# Sheet1.net
KiCad netlist of a schematic drawn in Altium Designer
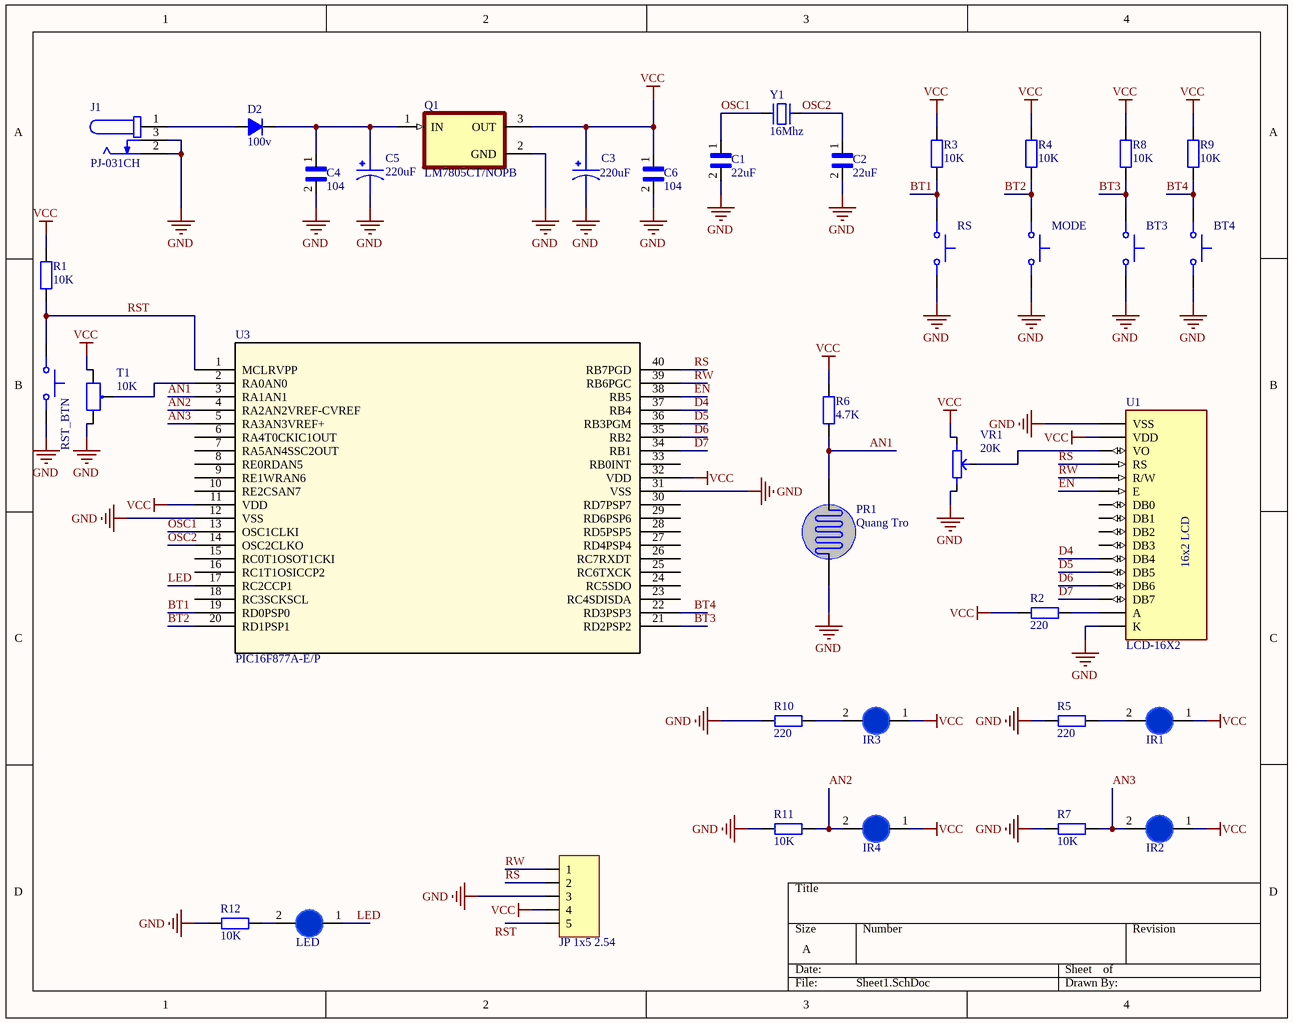
[diagram p0: Sheet1.SchDoc]

(export (version "E")
  (design (tool "Eeschema 10.0.6"))
  (components
    (comp (ref "BT3")
      (value "B3WN-6002")
      (footprint "SW_B3WN-6002")
      (description "Tactile Switch SPST-NO Top Actuated Through Hole")
      (fields (field (name "MF") "Omron Electronics"))
      (libsource (lib "button") (part "B3WN-6002"))
    )
    (comp (ref "BT4")
      (value "B3WN-6002")
      (footprint "SW_B3WN-6002")
      (description "Tactile Switch SPST-NO Top Actuated Through Hole")
      (fields (field (name "MF") "Omron Electronics"))
      (libsource (lib "button") (part "B3WN-6002"))
    )
    (comp (ref "C1")
      (value "22uF")
      (footprint "CAPRB250W50L550T350H600")
      (description "10 ÂµF Â±10% 50V Ceramic Capacitor X5R Radial")
      (fields (field (name "MF") "TDK") (field (name "MP") "FG16X5R1H106KRT00"))
      (libsource (lib "tu gom") (part "FG16X5R1H106KRT00"))
    )
    (comp (ref "C2")
      (value "22uF")
      (footprint "CAPRB250W50L550T350H600")
      (description "10 ÂµF Â±10% 50V Ceramic Capacitor X5R Radial")
      (fields (field (name "MF") "TDK") (field (name "MP") "FG16X5R1H106KRT00"))
      (libsource (lib "tu gom") (part "FG16X5R1H106KRT00"))
    )
    (comp (ref "C3")
      (value "220uF")
      (footprint "CAPPRD500W60D1330H2700")
      (description "4700 ÂµF 10 V Aluminum Electrolytic Capacitors Radial, Can 98.8mOhm @ 120Hz 2000 Hrs @ 85Â°C")
      (fields (field (name "MF") "Illinois Capacitor") (field (name "MP") "478CKS010M"))
      (libsource (lib "ALUCAP") (part "478CKS010M"))
    )
    (comp (ref "C4")
      (value "104")
      (footprint "CAPRB250W50L550T350H600")
      (description "10 ÂµF Â±10% 50V Ceramic Capacitor X5R Radial")
      (fields (field (name "MF") "TDK") (field (name "MP") "FG16X5R1H106KRT00"))
      (libsource (lib "tu gom") (part "FG16X5R1H106KRT00"))
    )
    (comp (ref "C5")
      (value "220uF")
      (footprint "CAPPRD500W60D1330H2700")
      (description "4700 ÂµF 10 V Aluminum Electrolytic Capacitors Radial, Can 98.8mOhm @ 120Hz 2000 Hrs @ 85Â°C")
      (fields (field (name "MF") "Illinois Capacitor") (field (name "MP") "478CKS010M"))
      (libsource (lib "ALUCAP") (part "478CKS010M"))
    )
    (comp (ref "C6")
      (value "104")
      (footprint "CAPRB250W50L550T350H600")
      (description "10 ÂµF Â±10% 50V Ceramic Capacitor X5R Radial")
      (fields (field (name "MF") "TDK") (field (name "MP") "FG16X5R1H106KRT00"))
      (libsource (lib "tu gom") (part "FG16X5R1H106KRT00"))
    )
    (comp (ref "D2")
      (value "100v")
      (footprint "DIODE 1A")
      (description "Cắm")
      (libsource (lib "Altium_Lib_by_KhueNguyenCreator") (part "Diode 1N4007"))
    )
    (comp (ref "IR1")
      (value "LED 3mm")
      (footprint "LED-3MM-BLUE")
      (description "Cắm")
      (libsource (lib "Altium_Lib_by_KhueNguyenCreator") (part "LED 3mm Xanh Duong"))
    )
    (comp (ref "IR2")
      (value "LED 3mm")
      (footprint "LED-3MM-BLUE")
      (description "Cắm")
      (libsource (lib "Altium_Lib_by_KhueNguyenCreator") (part "LED 3mm Xanh Duong"))
    )
    (comp (ref "IR3")
      (value "LED 3mm")
      (footprint "LED-3MM-BLUE")
      (description "Cắm")
      (libsource (lib "Altium_Lib_by_KhueNguyenCreator") (part "LED 3mm Xanh Duong"))
    )
    (comp (ref "IR4")
      (value "LED 3mm")
      (footprint "LED-3MM-BLUE")
      (description "Cắm")
      (libsource (lib "Altium_Lib_by_KhueNguyenCreator") (part "LED 3mm Xanh Duong"))
    )
    (comp (ref "J1")
      (value "PJ-031CH")
      (footprint "SAMESKY_PJ-031CH")
      (description "1.0 x 4 mm, 3.5 A, Horizontal, Through Hole, Dc Power Jack Connector")
      (fields (field (name "MF") "Same Sky"))
      (libsource (lib "JACK_DC") (part "PJ-031CH"))
    )
    (comp (ref "JP1")
      (value "JP 1x5 2.54")
      (footprint "JP 1x5 DC")
      (description "Cắm")
      (libsource (lib "Altium_Lib_by_KhueNguyenCreator") (part "JP 1x5 2.54 Duc Cong"))
    )
    (comp (ref "LED")
      (value "LED 3mm")
      (footprint "LED-3MM-BLUE")
      (description "Cắm")
      (libsource (lib "Altium_Lib_by_KhueNguyenCreator") (part "LED 3mm Xanh Duong"))
    )
    (comp (ref "MODE")
      (value "B3WN-6002")
      (footprint "SW_B3WN-6002")
      (description "Tactile Switch SPST-NO Top Actuated Through Hole")
      (fields (field (name "MF") "Omron Electronics"))
      (libsource (lib "button") (part "B3WN-6002"))
    )
    (comp (ref "PR1")
      (value "Quang Tro")
      (footprint "Quang Tro")
      (description "Photoresistor")
      (fields (field (name "CREATOR") "Bien Nguyen"))
      (libsource (lib "Altium_Lib_by_KhueNguyenCreator") (part "Quang Tro"))
    )
    (comp (ref "Q1")
      (value "LM7805CT/NOPB")
      (footprint "TO254P1054X470X2600-3")
      (description "Linear Voltage Regulator IC Positive Fixed 1 Output 1.5A TO-220-3")
      (fields (field (name "MF") "ON Semiconductor") (field (name "MP") "LM7805CT"))
      (libsource (lib "LM7805CT_NOPB") (part "LM7805CT/NOPB"))
    )
    (comp (ref "R1")
      (value "10K")
      (footprint "tro vach 1w")
      (description "Cắm")
      (libsource (lib "Altium_Lib_by_KhueNguyenCreator") (part "Tro Vach 1W 5% 470k"))
    )
    (comp (ref "R2")
      (value "220")
      (footprint "tro vach 1w")
      (description "Cắm")
      (libsource (lib "Altium_Lib_by_KhueNguyenCreator") (part "Tro Vach 1W 5% 470k"))
    )
    (comp (ref "R3")
      (value "10K")
      (footprint "tro vach 1w")
      (description "Cắm")
      (libsource (lib "Altium_Lib_by_KhueNguyenCreator") (part "Tro Vach 1W 5% 470k"))
    )
    (comp (ref "R4")
      (value "10K")
      (footprint "tro vach 1w")
      (description "Cắm")
      (libsource (lib "Altium_Lib_by_KhueNguyenCreator") (part "Tro Vach 1W 5% 470k"))
    )
    (comp (ref "R5")
      (value "220")
      (footprint "tro vach 1w")
      (description "Cắm")
      (libsource (lib "Altium_Lib_by_KhueNguyenCreator") (part "Tro Vach 1W 5% 470k"))
    )
    (comp (ref "R6")
      (value "4.7K")
      (footprint "tro vach 1w")
      (description "Cắm")
      (libsource (lib "Altium_Lib_by_KhueNguyenCreator") (part "Tro Vach 1W 5% 470k"))
    )
    (comp (ref "R7")
      (value "10K")
      (footprint "tro vach 1w")
      (description "Cắm")
      (libsource (lib "Altium_Lib_by_KhueNguyenCreator") (part "Tro Vach 1W 5% 470k"))
    )
    (comp (ref "R8")
      (value "10K")
      (footprint "tro vach 1w")
      (description "Cắm")
      (libsource (lib "Altium_Lib_by_KhueNguyenCreator") (part "Tro Vach 1W 5% 470k"))
    )
    (comp (ref "R9")
      (value "10K")
      (footprint "tro vach 1w")
      (description "Cắm")
      (libsource (lib "Altium_Lib_by_KhueNguyenCreator") (part "Tro Vach 1W 5% 470k"))
    )
    (comp (ref "R10")
      (value "220")
      (footprint "tro vach 1w")
      (description "Cắm")
      (libsource (lib "Altium_Lib_by_KhueNguyenCreator") (part "Tro Vach 1W 5% 470k"))
    )
    (comp (ref "R11")
      (value "10K")
      (footprint "tro vach 1w")
      (description "Cắm")
      (libsource (lib "Altium_Lib_by_KhueNguyenCreator") (part "Tro Vach 1W 5% 470k"))
    )
    (comp (ref "R12")
      (value "10K")
      (footprint "tro vach 1w")
      (description "Cắm")
      (libsource (lib "Altium_Lib_by_KhueNguyenCreator") (part "Tro Vach 1W 5% 470k"))
    )
    (comp (ref "RS")
      (value "B3WN-6002")
      (footprint "SW_B3WN-6002")
      (description "Tactile Switch SPST-NO Top Actuated Through Hole")
      (fields (field (name "MF") "Omron Electronics"))
      (libsource (lib "button") (part "B3WN-6002"))
    )
    (comp (ref "RST_BTN")
      (value "B3WN-6002")
      (footprint "SW_B3WN-6002")
      (description "Tactile Switch SPST-NO Top Actuated Through Hole")
      (fields (field (name "MF") "Omron Electronics"))
      (libsource (lib "button") (part "B3WN-6002"))
    )
    (comp (ref "T1")
      (value "10K")
      (footprint "Bien Tro Vi Chinh Dung")
      (description "Cắm")
      (libsource (lib "Altium_Lib_by_KhueNguyenCreator") (part "Bien Tro Tinh Chinh 100R Dung"))
    )
    (comp (ref "U1")
      (value "LCD-16X2")
      (footprint "MODULE_LCD-16X2")
      (description "Display Development Tools 16x2 Black on Green Char LCD w Backlight")
      (fields (field (name "MF") "Gravitech"))
      (libsource (lib "LCD-16X2") (part "LCD-16X2"))
    )
    (comp (ref "U3")
      (value "PIC16F877A-E/P")
      (footprint "PDIP40_600MC_MCH")
      (description "Description")
      (fields (field (name "COPYRIGHT") "Copyright (C) 2025 Ultra Librarian. All rights reserved."))
      (libsource (lib "PIC16F877A-EP") (part "PIC16F877A-EP"))
    )
    (comp (ref "VR1")
      (value "20K")
      (footprint "Bien Tro Tam Giac Nam")
      (description "Cắm")
      (libsource (lib "Altium_Lib_by_KhueNguyenCreator") (part "Bien tro tam giac 20K Nam"))
    )
    (comp (ref "Y1")
      (value "16Mhz")
      (footprint "Thach Anh 2 chan cam")
      (description "Crystal For all Crystal 2pin.")
      (libsource (lib "Altium_Lib_by_KhueNguyenCreator") (part "Thach Anh 2 chan Cam"))
    )
  )
  (nets
    (net (code "1") (name "/AN1") (class "Default")
      (node (ref "PR1") (pin "1") (pinfunction "1_1") (pintype "passive"))
      (node (ref "R6") (pin "2") (pinfunction "2_2") (pintype "passive"))
      (node (ref "U3") (pin "3") (pinfunction "RA1AN1_3") (pintype "passive"))
    )
    (net (code "2") (name "/AN2") (class "Default")
      (node (ref "IR4") (pin "2") (pinfunction "K_2") (pintype "passive"))
      (node (ref "R11") (pin "1") (pinfunction "1_1") (pintype "passive"))
      (node (ref "U3") (pin "4") (pinfunction "RA2AN2VREF-CVREF_4") (pintype "passive"))
    )
    (net (code "3") (name "/AN3") (class "Default")
      (node (ref "IR2") (pin "2") (pinfunction "K_2") (pintype "passive"))
      (node (ref "R7") (pin "1") (pinfunction "1_1") (pintype "passive"))
      (node (ref "U3") (pin "5") (pinfunction "RA3AN3VREF+_5") (pintype "passive"))
    )
    (net (code "4") (name "/BT1") (class "Default")
      (node (ref "R3") (pin "2") (pinfunction "2_2") (pintype "passive"))
      (node (ref "RS") (pin "1") (pinfunction "1_1") (pintype "passive"))
      (node (ref "U3") (pin "19") (pinfunction "RD0PSP0_19") (pintype "passive"))
    )
    (net (code "5") (name "/BT2") (class "Default")
      (node (ref "MODE") (pin "1") (pinfunction "1_1") (pintype "passive"))
      (node (ref "R4") (pin "2") (pinfunction "2_2") (pintype "passive"))
      (node (ref "U3") (pin "20") (pinfunction "RD1PSP1_20") (pintype "passive"))
    )
    (net (code "6") (name "/BT3") (class "Default")
      (node (ref "BT3") (pin "1") (pinfunction "1_1") (pintype "passive"))
      (node (ref "R8") (pin "2") (pinfunction "2_2") (pintype "passive"))
      (node (ref "U3") (pin "21") (pinfunction "RD2PSP2_21") (pintype "passive"))
    )
    (net (code "7") (name "/BT4") (class "Default")
      (node (ref "BT4") (pin "1") (pinfunction "1_1") (pintype "passive"))
      (node (ref "R9") (pin "2") (pinfunction "2_2") (pintype "passive"))
      (node (ref "U3") (pin "22") (pinfunction "RD3PSP3_22") (pintype "passive"))
    )
    (net (code "8") (name "/D4") (class "Default")
      (node (ref "U1") (pin "11") (pinfunction "DB4_11") (pintype "bidirectional"))
      (node (ref "U3") (pin "37") (pinfunction "RB4_37") (pintype "passive"))
    )
    (net (code "9") (name "/D5") (class "Default")
      (node (ref "U1") (pin "12") (pinfunction "DB5_12") (pintype "bidirectional"))
      (node (ref "U3") (pin "36") (pinfunction "RB3PGM_36") (pintype "passive"))
    )
    (net (code "10") (name "/D6") (class "Default")
      (node (ref "U1") (pin "13") (pinfunction "DB6_13") (pintype "bidirectional"))
      (node (ref "U3") (pin "35") (pinfunction "RB2_35") (pintype "passive"))
    )
    (net (code "11") (name "/D7") (class "Default")
      (node (ref "U1") (pin "14") (pinfunction "DB7_14") (pintype "bidirectional"))
      (node (ref "U3") (pin "34") (pinfunction "RB1_34") (pintype "passive"))
    )
    (net (code "12") (name "/EN") (class "Default")
      (node (ref "U1") (pin "6") (pinfunction "E_6") (pintype "input"))
      (node (ref "U3") (pin "38") (pinfunction "RB5_38") (pintype "passive"))
    )
    (net (code "13") (name "/LED") (class "Default")
      (node (ref "LED") (pin "1") (pinfunction "A_1") (pintype "passive"))
      (node (ref "U3") (pin "17") (pinfunction "RC2CCP1_17") (pintype "passive"))
    )
    (net (code "14") (name "/OSC1") (class "Default")
      (node (ref "C1") (pin "1") (pinfunction "1_1") (pintype "passive"))
      (node (ref "U3") (pin "13") (pinfunction "OSC1CLKI_13") (pintype "passive"))
      (node (ref "Y1") (pin "1") (pinfunction "1_1") (pintype "passive"))
    )
    (net (code "15") (name "/OSC2") (class "Default")
      (node (ref "C2") (pin "1") (pinfunction "1_1") (pintype "passive"))
      (node (ref "U3") (pin "14") (pinfunction "OSC2CLKO_14") (pintype "passive"))
      (node (ref "Y1") (pin "2") (pinfunction "2_2") (pintype "passive"))
    )
    (net (code "16") (name "/RS") (class "Default")
      (node (ref "JP1") (pin "2") (pinfunction "2_2") (pintype "passive"))
      (node (ref "U1") (pin "4") (pinfunction "RS_4") (pintype "input"))
      (node (ref "U3") (pin "40") (pinfunction "RB7PGD_40") (pintype "passive"))
    )
    (net (code "17") (name "/RST") (class "Default")
      (node (ref "JP1") (pin "5") (pinfunction "5_5") (pintype "passive"))
      (node (ref "R1") (pin "2") (pinfunction "2_2") (pintype "passive"))
      (node (ref "RST_BTN") (pin "1") (pinfunction "1_1") (pintype "passive"))
      (node (ref "U3") (pin "1") (pinfunction "MCLRVPP_1") (pintype "passive"))
    )
    (net (code "18") (name "/RW") (class "Default")
      (node (ref "JP1") (pin "1") (pinfunction "1_1") (pintype "passive"))
      (node (ref "U1") (pin "5") (pinfunction "R/W_5") (pintype "input"))
      (node (ref "U3") (pin "39") (pinfunction "RB6PGC_39") (pintype "passive"))
    )
    (net (code "19") (name "GND") (class "Default")
      (node (ref "BT3") (pin "2") (pinfunction "2_2") (pintype "passive"))
      (node (ref "BT4") (pin "2") (pinfunction "2_2") (pintype "passive"))
      (node (ref "C1") (pin "2") (pinfunction "2_2") (pintype "passive"))
      (node (ref "C2") (pin "2") (pinfunction "2_2") (pintype "passive"))
      (node (ref "C3") (pin "2") (pinfunction "2_2") (pintype "passive"))
      (node (ref "C4") (pin "2") (pinfunction "2_2") (pintype "passive"))
      (node (ref "C5") (pin "2") (pinfunction "2_2") (pintype "passive"))
      (node (ref "C6") (pin "2") (pinfunction "2_2") (pintype "passive"))
      (node (ref "J1") (pin "2") (pinfunction "2_2") (pintype "passive"))
      (node (ref "J1") (pin "3") (pinfunction "3_3") (pintype "passive"))
      (node (ref "JP1") (pin "3") (pinfunction "3_3") (pintype "passive"))
      (node (ref "MODE") (pin "2") (pinfunction "2_2") (pintype "passive"))
      (node (ref "PR1") (pin "2") (pinfunction "2_2") (pintype "passive"))
      (node (ref "Q1") (pin "2") (pinfunction "GND_2") (pintype "power_in"))
      (node (ref "R10") (pin "2") (pinfunction "2_2") (pintype "passive"))
      (node (ref "R11") (pin "2") (pinfunction "2_2") (pintype "passive"))
      (node (ref "R12") (pin "2") (pinfunction "2_2") (pintype "passive"))
      (node (ref "R5") (pin "2") (pinfunction "2_2") (pintype "passive"))
      (node (ref "R7") (pin "2") (pinfunction "2_2") (pintype "passive"))
      (node (ref "RS") (pin "2") (pinfunction "2_2") (pintype "passive"))
      (node (ref "RST_BTN") (pin "2") (pinfunction "2_2") (pintype "passive"))
      (node (ref "T1") (pin "3") (pinfunction "3_3") (pintype "passive"))
      (node (ref "U1") (pin "1") (pinfunction "VSS_1") (pintype "power_in"))
      (node (ref "U1") (pin "16") (pinfunction "K_16") (pintype "power_in"))
      (node (ref "U3") (pin "12") (pinfunction "VSS_12") (pintype "passive"))
      (node (ref "U3") (pin "31") (pinfunction "VSS_31") (pintype "passive"))
      (node (ref "VR1") (pin "3") (pinfunction "3_3") (pintype "passive"))
    )
    (net (code "20") (name "Net-(D2-A)") (class "Default")
      (node (ref "D2") (pin "1") (pinfunction "A_1") (pintype "passive"))
      (node (ref "J1") (pin "1") (pinfunction "1_1") (pintype "passive"))
    )
    (net (code "21") (name "Net-(D2-K)") (class "Default")
      (node (ref "C4") (pin "1") (pinfunction "1_1") (pintype "passive"))
      (node (ref "C5") (pin "1") (pinfunction "1_1") (pintype "passive"))
      (node (ref "D2") (pin "2") (pinfunction "K_2") (pintype "passive"))
      (node (ref "Q1") (pin "1") (pinfunction "IN_1") (pintype "input"))
    )
    (net (code "22") (name "Net-(IR1-K)") (class "Default")
      (node (ref "IR1") (pin "2") (pinfunction "K_2") (pintype "passive"))
      (node (ref "R5") (pin "1") (pinfunction "1_1") (pintype "passive"))
    )
    (net (code "23") (name "Net-(IR3-K)") (class "Default")
      (node (ref "IR3") (pin "2") (pinfunction "K_2") (pintype "passive"))
      (node (ref "R10") (pin "1") (pinfunction "1_1") (pintype "passive"))
    )
    (net (code "24") (name "Net-(LED-K)") (class "Default")
      (node (ref "LED") (pin "2") (pinfunction "K_2") (pintype "passive"))
      (node (ref "R12") (pin "1") (pinfunction "1_1") (pintype "passive"))
    )
    (net (code "25") (name "Net-(U1-A)") (class "Default")
      (node (ref "R2") (pin "1") (pinfunction "1_1") (pintype "passive"))
      (node (ref "U1") (pin "15") (pinfunction "A_15") (pintype "power_in"))
    )
    (net (code "26") (name "Net-(U1-VO)") (class "Default")
      (node (ref "U1") (pin "3") (pinfunction "VO_3") (pintype "bidirectional"))
      (node (ref "VR1") (pin "2") (pinfunction "2_2") (pintype "passive"))
    )
    (net (code "27") (name "Net-(U3-RA0AN0)") (class "Default")
      (node (ref "T1") (pin "2") (pinfunction "2_2") (pintype "passive"))
      (node (ref "U3") (pin "2") (pinfunction "RA0AN0_2") (pintype "passive"))
    )
    (net (code "28") (name "VCC") (class "Default")
      (node (ref "C3") (pin "1") (pinfunction "1_1") (pintype "passive"))
      (node (ref "C6") (pin "1") (pinfunction "1_1") (pintype "passive"))
      (node (ref "IR1") (pin "1") (pinfunction "A_1") (pintype "passive"))
      (node (ref "IR2") (pin "1") (pinfunction "A_1") (pintype "passive"))
      (node (ref "IR3") (pin "1") (pinfunction "A_1") (pintype "passive"))
      (node (ref "IR4") (pin "1") (pinfunction "A_1") (pintype "passive"))
      (node (ref "JP1") (pin "4") (pinfunction "4_4") (pintype "passive"))
      (node (ref "Q1") (pin "3") (pinfunction "OUT_3") (pintype "power_in"))
      (node (ref "R1") (pin "1") (pinfunction "1_1") (pintype "passive"))
      (node (ref "R2") (pin "2") (pinfunction "2_2") (pintype "passive"))
      (node (ref "R3") (pin "1") (pinfunction "1_1") (pintype "passive"))
      (node (ref "R4") (pin "1") (pinfunction "1_1") (pintype "passive"))
      (node (ref "R6") (pin "1") (pinfunction "1_1") (pintype "passive"))
      (node (ref "R8") (pin "1") (pinfunction "1_1") (pintype "passive"))
      (node (ref "R9") (pin "1") (pinfunction "1_1") (pintype "passive"))
      (node (ref "T1") (pin "1") (pinfunction "1_1") (pintype "passive"))
      (node (ref "U1") (pin "2") (pinfunction "VDD_2") (pintype "power_in"))
      (node (ref "U3") (pin "11") (pinfunction "VDD_11") (pintype "passive"))
      (node (ref "U3") (pin "32") (pinfunction "VDD_32") (pintype "passive"))
      (node (ref "VR1") (pin "1") (pinfunction "1_1") (pintype "passive"))
    )
    (net (code "29") (name "unconnected-(U1-DB0-Pad7)") (class "Default")
      (node (ref "U1") (pin "7") (pinfunction "DB0_7") (pintype "bidirectional"))
    )
    (net (code "30") (name "unconnected-(U1-DB1-Pad8)") (class "Default")
      (node (ref "U1") (pin "8") (pinfunction "DB1_8") (pintype "bidirectional"))
    )
    (net (code "31") (name "unconnected-(U1-DB2-Pad9)") (class "Default")
      (node (ref "U1") (pin "9") (pinfunction "DB2_9") (pintype "bidirectional"))
    )
    (net (code "32") (name "unconnected-(U1-DB3-Pad10)") (class "Default")
      (node (ref "U1") (pin "10") (pinfunction "DB3_10") (pintype "bidirectional"))
    )
    (net (code "33") (name "unconnected-(U3-RA4T0CKIC1OUT-Pad6)") (class "Default")
      (node (ref "U3") (pin "6") (pinfunction "RA4T0CKIC1OUT_6") (pintype "passive"))
    )
    (net (code "34") (name "unconnected-(U3-RA5AN4SSC2OUT-Pad7)") (class "Default")
      (node (ref "U3") (pin "7") (pinfunction "RA5AN4SSC2OUT_7") (pintype "passive"))
    )
    (net (code "35") (name "unconnected-(U3-RB0INT-Pad33)") (class "Default")
      (node (ref "U3") (pin "33") (pinfunction "RB0INT_33") (pintype "passive"))
    )
    (net (code "36") (name "unconnected-(U3-RC0T1OSOT1CKI-Pad15)") (class "Default")
      (node (ref "U3") (pin "15") (pinfunction "RC0T1OSOT1CKI_15") (pintype "passive"))
    )
    (net (code "37") (name "unconnected-(U3-RC1T1OSICCP2-Pad16)") (class "Default")
      (node (ref "U3") (pin "16") (pinfunction "RC1T1OSICCP2_16") (pintype "passive"))
    )
    (net (code "38") (name "unconnected-(U3-RC3SCKSCL-Pad18)") (class "Default")
      (node (ref "U3") (pin "18") (pinfunction "RC3SCKSCL_18") (pintype "passive"))
    )
    (net (code "39") (name "unconnected-(U3-RC4SDISDA-Pad23)") (class "Default")
      (node (ref "U3") (pin "23") (pinfunction "RC4SDISDA_23") (pintype "passive"))
    )
    (net (code "40") (name "unconnected-(U3-RC5SDO-Pad24)") (class "Default")
      (node (ref "U3") (pin "24") (pinfunction "RC5SDO_24") (pintype "passive"))
    )
    (net (code "41") (name "unconnected-(U3-RC6TXCK-Pad25)") (class "Default")
      (node (ref "U3") (pin "25") (pinfunction "RC6TXCK_25") (pintype "passive"))
    )
    (net (code "42") (name "unconnected-(U3-RC7RXDT-Pad26)") (class "Default")
      (node (ref "U3") (pin "26") (pinfunction "RC7RXDT_26") (pintype "passive"))
    )
    (net (code "43") (name "unconnected-(U3-RD4PSP4-Pad27)") (class "Default")
      (node (ref "U3") (pin "27") (pinfunction "RD4PSP4_27") (pintype "passive"))
    )
    (net (code "44") (name "unconnected-(U3-RD5PSP5-Pad28)") (class "Default")
      (node (ref "U3") (pin "28") (pinfunction "RD5PSP5_28") (pintype "passive"))
    )
    (net (code "45") (name "unconnected-(U3-RD6PSP6-Pad29)") (class "Default")
      (node (ref "U3") (pin "29") (pinfunction "RD6PSP6_29") (pintype "passive"))
    )
    (net (code "46") (name "unconnected-(U3-RD7PSP7-Pad30)") (class "Default")
      (node (ref "U3") (pin "30") (pinfunction "RD7PSP7_30") (pintype "passive"))
    )
    (net (code "47") (name "unconnected-(U3-RE0RDAN5-Pad8)") (class "Default")
      (node (ref "U3") (pin "8") (pinfunction "RE0RDAN5_8") (pintype "passive"))
    )
    (net (code "48") (name "unconnected-(U3-RE1WRAN6-Pad9)") (class "Default")
      (node (ref "U3") (pin "9") (pinfunction "RE1WRAN6_9") (pintype "passive"))
    )
    (net (code "49") (name "unconnected-(U3-RE2CSAN7-Pad10)") (class "Default")
      (node (ref "U3") (pin "10") (pinfunction "RE2CSAN7_10") (pintype "passive"))
    )
  )
)
